# rhoby_motor_L6205.net
KiCad netlist of a schematic drawn in EAGLE
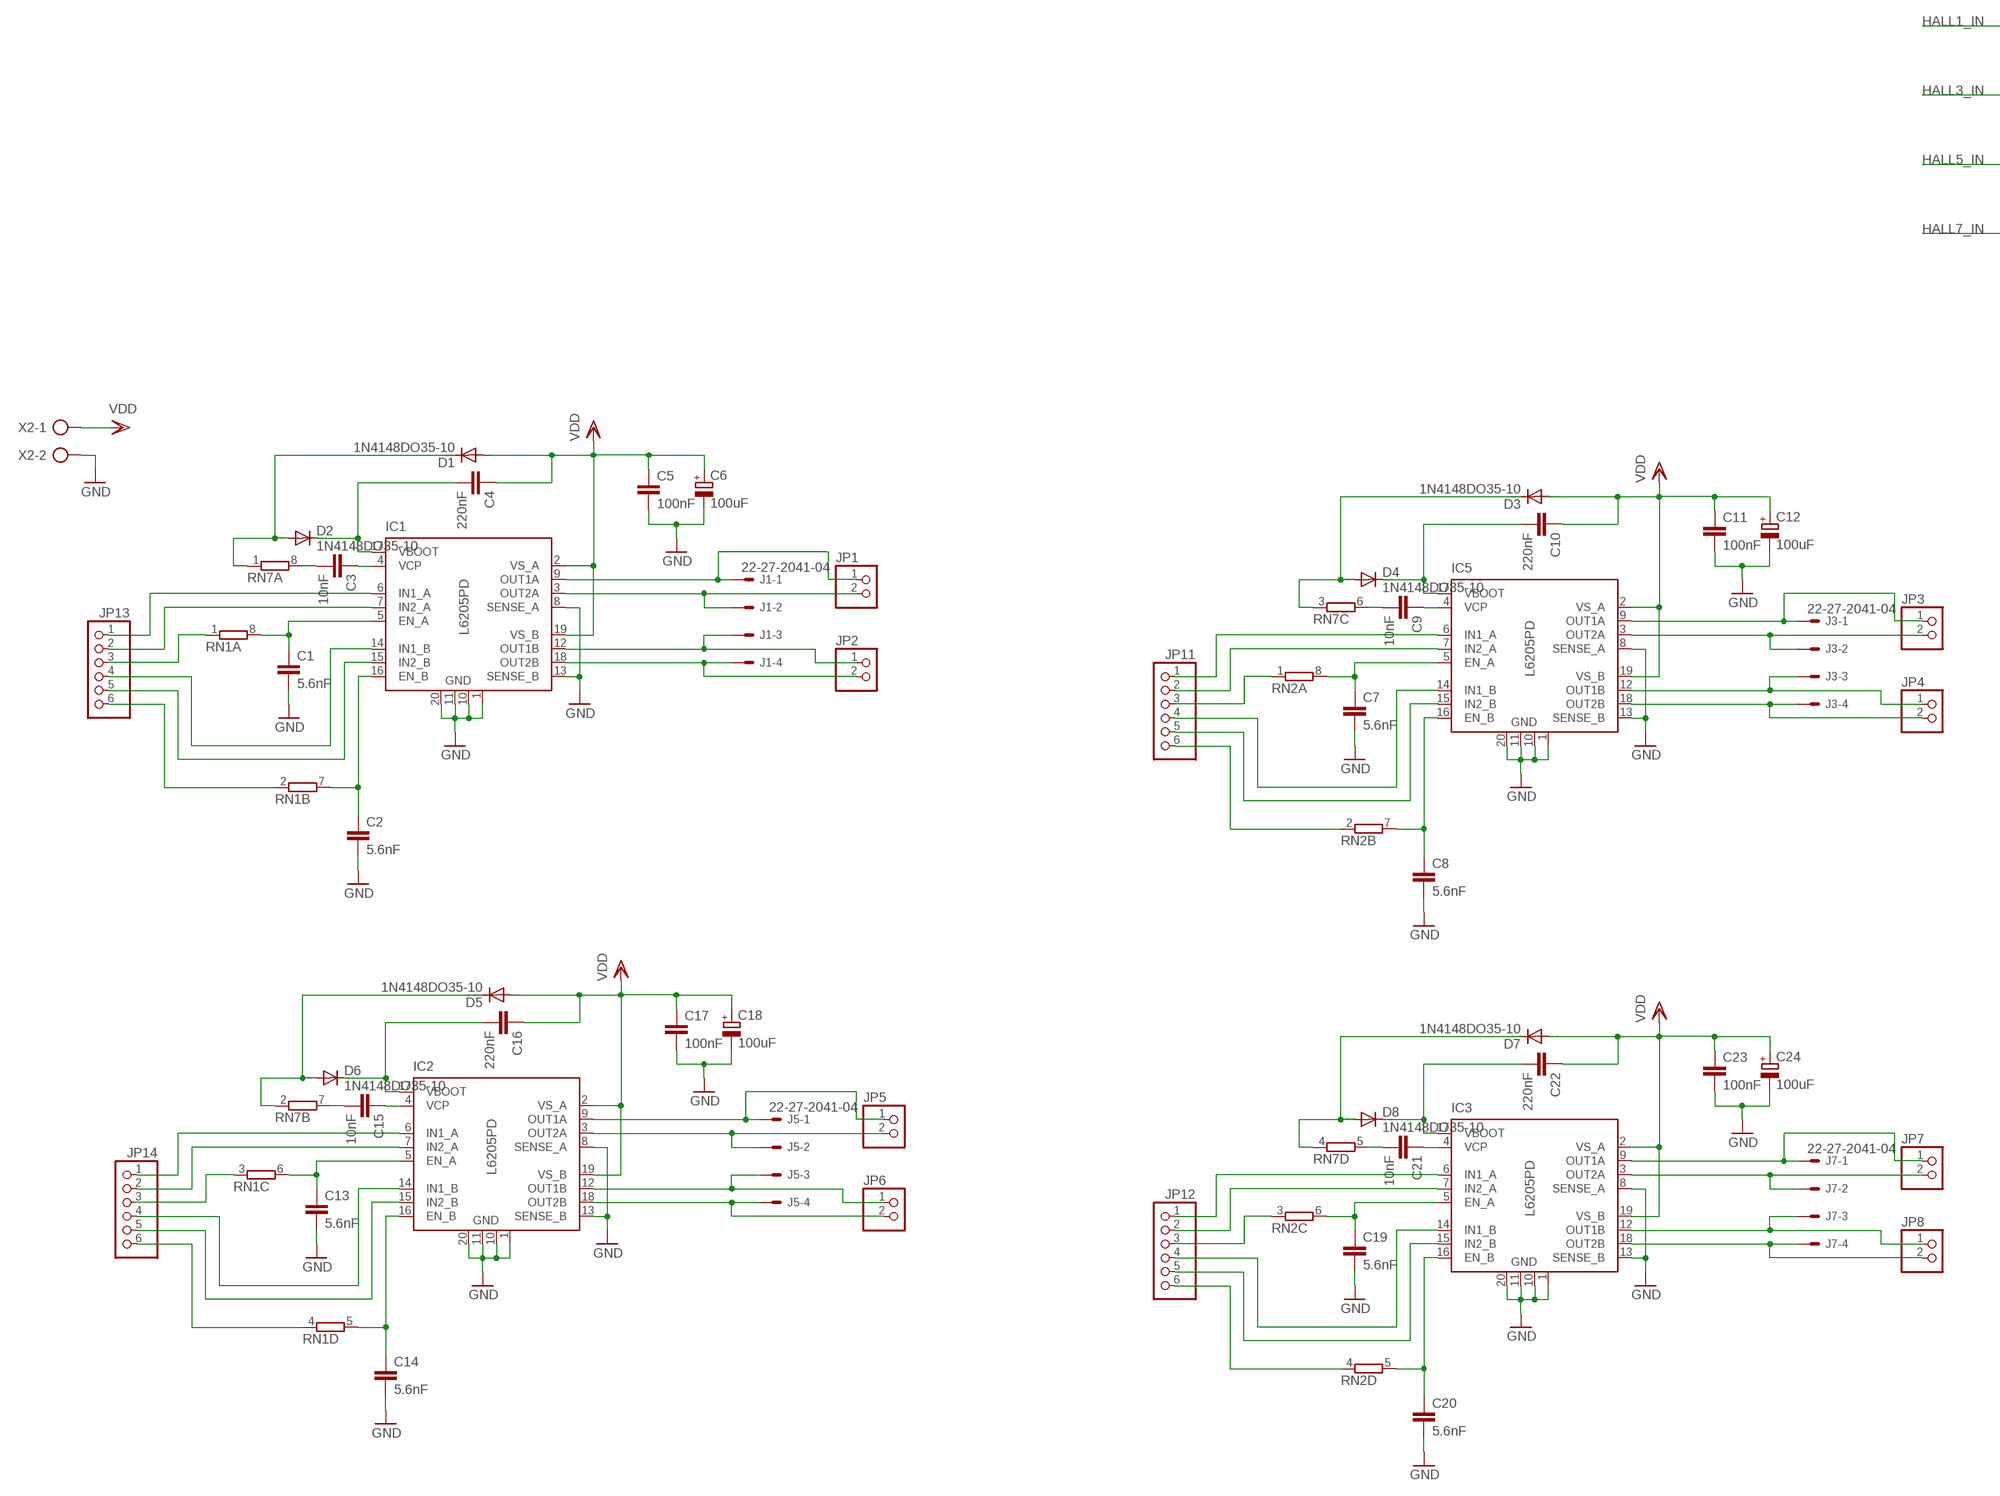
[diagram p0: schematic, sheet 1, part 1 of 2]
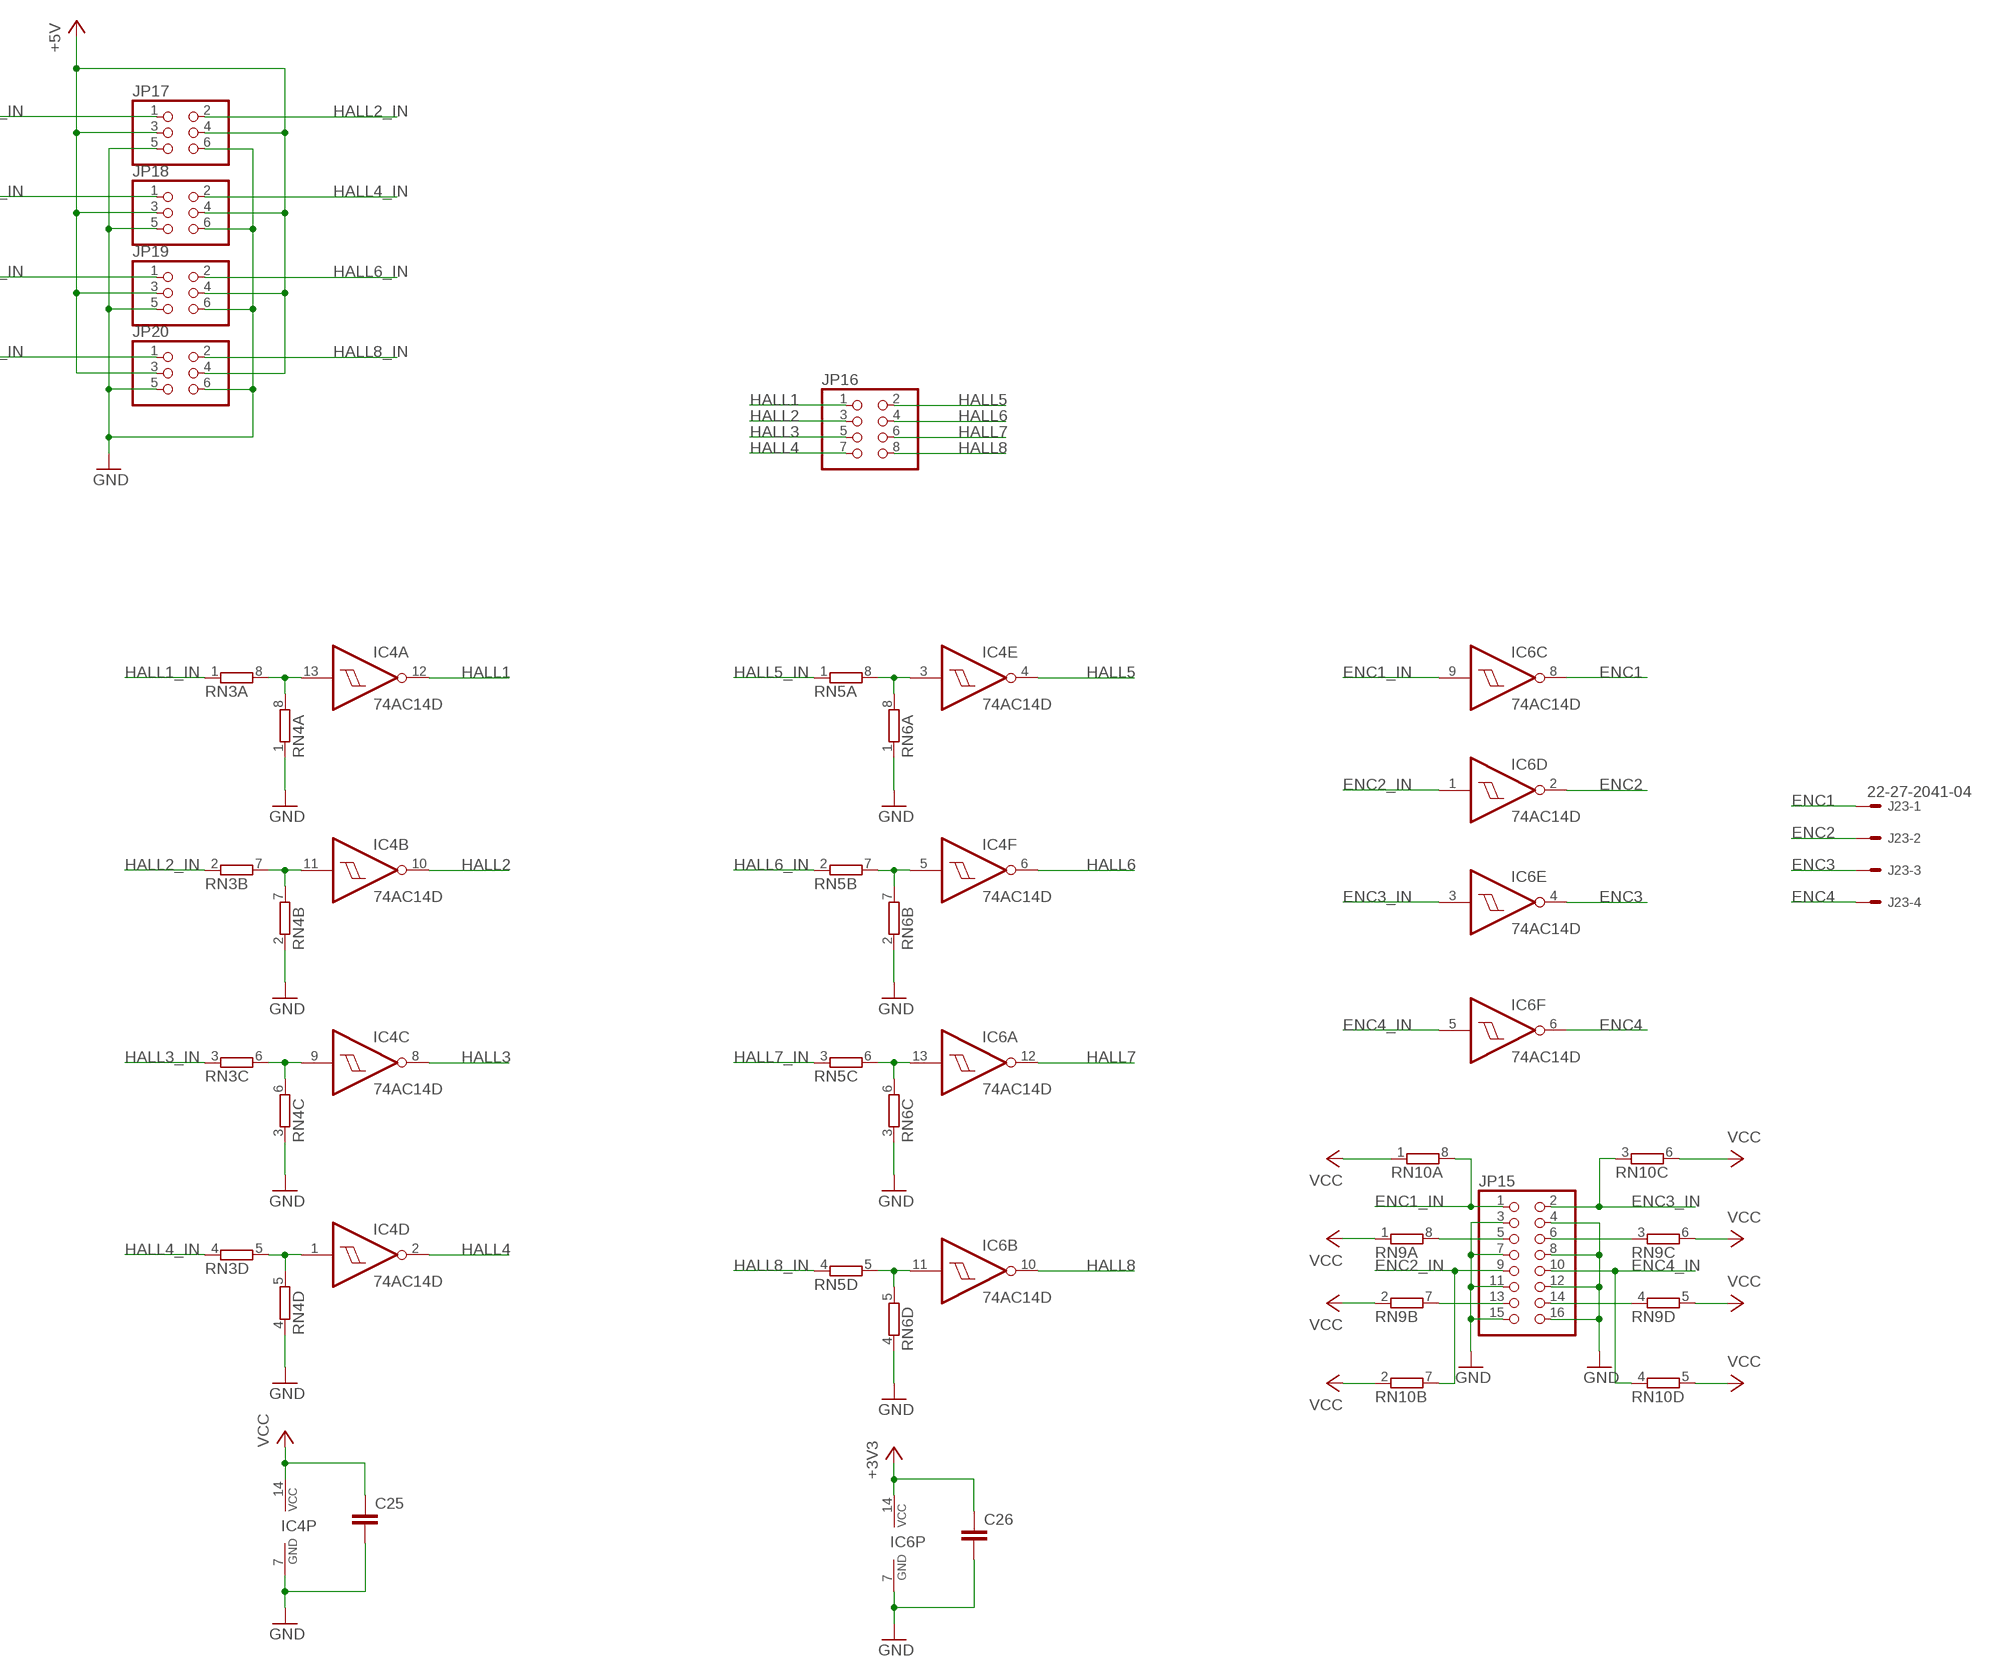
[diagram p1: schematic, sheet 1, part 2 of 2]

(export (version "E")
  (design (tool "Eeschema 10.0.6"))
  (components
    (comp (ref "C1")
      (value "5.6nF")
      (footprint "eagle-import:C0603K")
      (libsource (lib "eagle-import") (part "C-EUC0603K"))
    )
    (comp (ref "C2")
      (value "5.6nF")
      (footprint "eagle-import:C0603K")
      (libsource (lib "eagle-import") (part "C-EUC0603K"))
    )
    (comp (ref "C3")
      (value "10nF")
      (footprint "eagle-import:C0805K")
      (libsource (lib "eagle-import") (part "C-EUC0805K"))
    )
    (comp (ref "C4")
      (value "220nF")
      (footprint "eagle-import:C0805K")
      (libsource (lib "eagle-import") (part "C-EUC0805K"))
    )
    (comp (ref "C5")
      (value "100nF")
      (footprint "eagle-import:C2220K")
      (libsource (lib "eagle-import") (part "C-EUC2220K"))
    )
    (comp (ref "C6")
      (value "100uF")
      (footprint "eagle-import:SMC_D")
      (libsource (lib "eagle-import") (part "CPOL-EUSMCD"))
    )
    (comp (ref "C7")
      (value "5.6nF")
      (footprint "eagle-import:C0603K")
      (libsource (lib "eagle-import") (part "C-EUC0603K"))
    )
    (comp (ref "C8")
      (value "5.6nF")
      (footprint "eagle-import:C0603K")
      (libsource (lib "eagle-import") (part "C-EUC0603K"))
    )
    (comp (ref "C9")
      (value "10nF")
      (footprint "eagle-import:C0805K")
      (libsource (lib "eagle-import") (part "C-EUC0805K"))
    )
    (comp (ref "C10")
      (value "220nF")
      (footprint "eagle-import:C0805K")
      (libsource (lib "eagle-import") (part "C-EUC0805K"))
    )
    (comp (ref "C11")
      (value "100nF")
      (footprint "eagle-import:C2220K")
      (libsource (lib "eagle-import") (part "C-EUC2220K"))
    )
    (comp (ref "C12")
      (value "100uF")
      (footprint "eagle-import:SMC_D")
      (libsource (lib "eagle-import") (part "CPOL-EUSMCD"))
    )
    (comp (ref "C13")
      (value "5.6nF")
      (footprint "eagle-import:C0603K")
      (libsource (lib "eagle-import") (part "C-EUC0603K"))
    )
    (comp (ref "C14")
      (value "5.6nF")
      (footprint "eagle-import:C0603K")
      (libsource (lib "eagle-import") (part "C-EUC0603K"))
    )
    (comp (ref "C15")
      (value "10nF")
      (footprint "eagle-import:C0805K")
      (libsource (lib "eagle-import") (part "C-EUC0805K"))
    )
    (comp (ref "C16")
      (value "220nF")
      (footprint "eagle-import:C0805K")
      (libsource (lib "eagle-import") (part "C-EUC0805K"))
    )
    (comp (ref "C17")
      (value "100nF")
      (footprint "eagle-import:C2220K")
      (libsource (lib "eagle-import") (part "C-EUC2220K"))
    )
    (comp (ref "C18")
      (value "100uF")
      (footprint "eagle-import:SMC_D")
      (libsource (lib "eagle-import") (part "CPOL-EUSMCD"))
    )
    (comp (ref "C19")
      (value "5.6nF")
      (footprint "eagle-import:C0603K")
      (libsource (lib "eagle-import") (part "C-EUC0603K"))
    )
    (comp (ref "C20")
      (value "5.6nF")
      (footprint "eagle-import:C0603K")
      (libsource (lib "eagle-import") (part "C-EUC0603K"))
    )
    (comp (ref "C21")
      (value "10nF")
      (footprint "eagle-import:C0805K")
      (libsource (lib "eagle-import") (part "C-EUC0805K"))
    )
    (comp (ref "C22")
      (value "220nF")
      (footprint "eagle-import:C0805K")
      (libsource (lib "eagle-import") (part "C-EUC0805K"))
    )
    (comp (ref "C23")
      (value "100nF")
      (footprint "eagle-import:C2220K")
      (libsource (lib "eagle-import") (part "C-EUC2220K"))
    )
    (comp (ref "C24")
      (value "100uF")
      (footprint "eagle-import:SMC_D")
      (libsource (lib "eagle-import") (part "CPOL-EUSMCD"))
    )
    (comp (ref "C25")
      (value "C-EUC0603K")
      (footprint "eagle-import:C0603K")
      (libsource (lib "eagle-import") (part "C-EUC0603K"))
    )
    (comp (ref "C26")
      (value "C-EUC0603K")
      (footprint "eagle-import:C0603K")
      (libsource (lib "eagle-import") (part "C-EUC0603K"))
    )
    (comp (ref "D1")
      (value "1N4148DO35-10")
      (footprint "eagle-import:DO35-10")
      (libsource (lib "eagle-import") (part "1N4148DO35-10"))
    )
    (comp (ref "D2")
      (value "1N4148DO35-10")
      (footprint "eagle-import:DO35-10")
      (libsource (lib "eagle-import") (part "1N4148DO35-10"))
    )
    (comp (ref "D3")
      (value "1N4148DO35-10")
      (footprint "eagle-import:DO35-10")
      (libsource (lib "eagle-import") (part "1N4148DO35-10"))
    )
    (comp (ref "D4")
      (value "1N4148DO35-10")
      (footprint "eagle-import:DO35-10")
      (libsource (lib "eagle-import") (part "1N4148DO35-10"))
    )
    (comp (ref "D5")
      (value "1N4148DO35-10")
      (footprint "eagle-import:DO35-10")
      (libsource (lib "eagle-import") (part "1N4148DO35-10"))
    )
    (comp (ref "D6")
      (value "1N4148DO35-10")
      (footprint "eagle-import:DO35-10")
      (libsource (lib "eagle-import") (part "1N4148DO35-10"))
    )
    (comp (ref "D7")
      (value "1N4148DO35-10")
      (footprint "eagle-import:DO35-10")
      (libsource (lib "eagle-import") (part "1N4148DO35-10"))
    )
    (comp (ref "D8")
      (value "1N4148DO35-10")
      (footprint "eagle-import:DO35-10")
      (libsource (lib "eagle-import") (part "1N4148DO35-10"))
    )
    (comp (ref "IC1")
      (value "L6205PD")
      (footprint "eagle-import:POWERSO-20")
      (fields (field (name "MF") "Arrow Electronics"))
      (libsource (lib "eagle-import") (part "L6205PD"))
    )
    (comp (ref "IC2")
      (value "L6205PD")
      (footprint "eagle-import:POWERSO-20")
      (fields (field (name "MF") "Arrow Electronics"))
      (libsource (lib "eagle-import") (part "L6205PD"))
    )
    (comp (ref "IC3")
      (value "L6205PD")
      (footprint "eagle-import:POWERSO-20")
      (fields (field (name "MF") "Arrow Electronics"))
      (libsource (lib "eagle-import") (part "L6205PD"))
    )
    (comp (ref "IC4")
      (value "74AC14D")
      (footprint "eagle-import:SO14")
      (libsource (lib "eagle-import") (part "7414DAC"))
    )
    (comp (ref "IC5")
      (value "L6205PD")
      (footprint "eagle-import:POWERSO-20")
      (fields (field (name "MF") "Arrow Electronics"))
      (libsource (lib "eagle-import") (part "L6205PD"))
    )
    (comp (ref "IC6")
      (value "74AC14D")
      (footprint "eagle-import:SO14")
      (fields (field (name "SPICEPREFIX") "I"))
      (libsource (lib "eagle-import") (part "7414DAC"))
    )
    (comp (ref "J1")
      (value "22-27-2041-04")
      (footprint "eagle-import:6410-04")
      (fields (field (name "MF") "MOLEX"))
      (libsource (lib "eagle-import") (part "22-?-0427-2041"))
    )
    (comp (ref "J3")
      (value "22-27-2041-04")
      (footprint "eagle-import:6410-04")
      (fields (field (name "MF") "MOLEX"))
      (libsource (lib "eagle-import") (part "22-?-0427-2041"))
    )
    (comp (ref "J5")
      (value "22-27-2041-04")
      (footprint "eagle-import:6410-04")
      (fields (field (name "MF") "MOLEX"))
      (libsource (lib "eagle-import") (part "22-?-0427-2041"))
    )
    (comp (ref "J7")
      (value "22-27-2041-04")
      (footprint "eagle-import:6410-04")
      (fields (field (name "MF") "MOLEX"))
      (libsource (lib "eagle-import") (part "22-?-0427-2041"))
    )
    (comp (ref "J23")
      (value "22-27-2041-04")
      (footprint "eagle-import:6410-04")
      (fields (field (name "MF") "MOLEX"))
      (libsource (lib "eagle-import") (part "22-?-0427-2041"))
    )
    (comp (ref "JP1")
      (value "PINHD-1X2")
      (footprint "eagle-import:1X02")
      (libsource (lib "eagle-import") (part "PINHD-1X2"))
    )
    (comp (ref "JP2")
      (value "PINHD-1X2")
      (footprint "eagle-import:1X02")
      (libsource (lib "eagle-import") (part "PINHD-1X2"))
    )
    (comp (ref "JP3")
      (value "PINHD-1X2")
      (footprint "eagle-import:1X02")
      (libsource (lib "eagle-import") (part "PINHD-1X2"))
    )
    (comp (ref "JP4")
      (value "PINHD-1X2")
      (footprint "eagle-import:1X02")
      (libsource (lib "eagle-import") (part "PINHD-1X2"))
    )
    (comp (ref "JP5")
      (value "PINHD-1X2")
      (footprint "eagle-import:1X02")
      (libsource (lib "eagle-import") (part "PINHD-1X2"))
    )
    (comp (ref "JP6")
      (value "PINHD-1X2")
      (footprint "eagle-import:1X02")
      (libsource (lib "eagle-import") (part "PINHD-1X2"))
    )
    (comp (ref "JP7")
      (value "PINHD-1X2")
      (footprint "eagle-import:1X02")
      (libsource (lib "eagle-import") (part "PINHD-1X2"))
    )
    (comp (ref "JP8")
      (value "PINHD-1X2")
      (footprint "eagle-import:1X02")
      (libsource (lib "eagle-import") (part "PINHD-1X2"))
    )
    (comp (ref "JP11")
      (value "PINHD-1X6")
      (footprint "eagle-import:1X06")
      (libsource (lib "eagle-import") (part "PINHD-1X6"))
    )
    (comp (ref "JP12")
      (value "PINHD-1X6")
      (footprint "eagle-import:1X06")
      (libsource (lib "eagle-import") (part "PINHD-1X6"))
    )
    (comp (ref "JP13")
      (value "PINHD-1X6")
      (footprint "eagle-import:1X06")
      (libsource (lib "eagle-import") (part "PINHD-1X6"))
    )
    (comp (ref "JP14")
      (value "PINHD-1X6")
      (footprint "eagle-import:1X06")
      (libsource (lib "eagle-import") (part "PINHD-1X6"))
    )
    (comp (ref "JP15")
      (value "PINHD-2X8")
      (footprint "eagle-import:2X08")
      (libsource (lib "eagle-import") (part "PINHD-2X8"))
    )
    (comp (ref "JP16")
      (value "PINHD-2X4")
      (footprint "eagle-import:2X04")
      (libsource (lib "eagle-import") (part "PINHD-2X4"))
    )
    (comp (ref "JP17")
      (value "PINHD-2X3")
      (footprint "eagle-import:2X03")
      (libsource (lib "eagle-import") (part "PINHD-2X3"))
    )
    (comp (ref "JP18")
      (value "PINHD-2X3")
      (footprint "eagle-import:2X03")
      (libsource (lib "eagle-import") (part "PINHD-2X3"))
    )
    (comp (ref "JP19")
      (value "PINHD-2X3")
      (footprint "eagle-import:2X03")
      (libsource (lib "eagle-import") (part "PINHD-2X3"))
    )
    (comp (ref "JP20")
      (value "PINHD-2X3")
      (footprint "eagle-import:2X03")
      (libsource (lib "eagle-import") (part "PINHD-2X3"))
    )
    (comp (ref "RN1")
      (value "4R-NEXB38V")
      (footprint "eagle-import:EXB38V")
      (libsource (lib "eagle-import") (part "4R-NEXB38V"))
    )
    (comp (ref "RN2")
      (value "4R-NEXB38V")
      (footprint "eagle-import:EXB38V")
      (libsource (lib "eagle-import") (part "4R-NEXB38V"))
    )
    (comp (ref "RN3")
      (value "4R-NEXB38V")
      (footprint "eagle-import:EXB38V")
      (libsource (lib "eagle-import") (part "4R-NEXB38V"))
    )
    (comp (ref "RN4")
      (value "4R-NEXB38V")
      (footprint "eagle-import:EXB38V")
      (libsource (lib "eagle-import") (part "4R-NEXB38V"))
    )
    (comp (ref "RN5")
      (value "4R-NEXB38V")
      (footprint "eagle-import:EXB38V")
      (libsource (lib "eagle-import") (part "4R-NEXB38V"))
    )
    (comp (ref "RN6")
      (value "4R-NEXB38V")
      (footprint "eagle-import:EXB38V")
      (libsource (lib "eagle-import") (part "4R-NEXB38V"))
    )
    (comp (ref "RN7")
      (value "4R-NEXB38V")
      (footprint "eagle-import:EXB38V")
      (libsource (lib "eagle-import") (part "4R-NEXB38V"))
    )
    (comp (ref "RN9")
      (value "4R-NEXB38V")
      (footprint "eagle-import:EXB38V")
      (libsource (lib "eagle-import") (part "4R-NEXB38V"))
    )
    (comp (ref "RN10")
      (value "4R-NEXB38V")
      (footprint "eagle-import:EXB38V")
      (libsource (lib "eagle-import") (part "4R-NEXB38V"))
    )
    (comp (ref "X2")
      (value "AK500/2")
      (footprint "eagle-import:AK500_2")
      (libsource (lib "eagle-import") (part "AK500/2"))
    )
  )
  (nets
    (net (code "1") (name "+3V3") (class "Default")
      (node (ref "C26") (pin "1") (pinfunction "1_1") (pintype "passive"))
      (node (ref "IC6") (pin "14") (pinfunction "VCC_14") (pintype "power_in"))
    )
    (net (code "2") (name "+5V") (class "Default")
      (node (ref "JP17") (pin "3") (pinfunction "3_3") (pintype "passive"))
      (node (ref "JP17") (pin "4") (pinfunction "4_4") (pintype "passive"))
      (node (ref "JP18") (pin "3") (pinfunction "3_3") (pintype "passive"))
      (node (ref "JP18") (pin "4") (pinfunction "4_4") (pintype "passive"))
      (node (ref "JP19") (pin "3") (pinfunction "3_3") (pintype "passive"))
      (node (ref "JP19") (pin "4") (pinfunction "4_4") (pintype "passive"))
      (node (ref "JP20") (pin "3") (pinfunction "3_3") (pintype "passive"))
      (node (ref "JP20") (pin "4") (pinfunction "4_4") (pintype "passive"))
    )
    (net (code "3") (name "/ENC1") (class "Default")
      (node (ref "IC6") (pin "8") (pinfunction "O_8") (pintype "output"))
      (node (ref "J23") (pin "1") (pinfunction "S_1") (pintype "passive"))
    )
    (net (code "4") (name "/ENC1_IN") (class "Default")
      (node (ref "IC6") (pin "9") (pinfunction "I_9") (pintype "input"))
      (node (ref "JP15") (pin "1") (pinfunction "1_1") (pintype "passive"))
      (node (ref "RN10") (pin "8") (pinfunction "2_8") (pintype "passive"))
    )
    (net (code "5") (name "/ENC2") (class "Default")
      (node (ref "IC6") (pin "2") (pinfunction "O_2") (pintype "output"))
      (node (ref "J23") (pin "2") (pinfunction "S_2") (pintype "passive"))
    )
    (net (code "6") (name "/ENC2_IN") (class "Default")
      (node (ref "IC6") (pin "1") (pinfunction "I_1") (pintype "input"))
      (node (ref "JP15") (pin "9") (pinfunction "9_9") (pintype "passive"))
      (node (ref "RN10") (pin "7") (pinfunction "2_7") (pintype "passive"))
    )
    (net (code "7") (name "/ENC3") (class "Default")
      (node (ref "IC6") (pin "4") (pinfunction "O_4") (pintype "output"))
      (node (ref "J23") (pin "3") (pinfunction "S_3") (pintype "passive"))
    )
    (net (code "8") (name "/ENC3_IN") (class "Default")
      (node (ref "IC6") (pin "3") (pinfunction "I_3") (pintype "input"))
      (node (ref "JP15") (pin "2") (pinfunction "2_2") (pintype "passive"))
      (node (ref "RN10") (pin "3") (pinfunction "1_3") (pintype "passive"))
    )
    (net (code "9") (name "/ENC4") (class "Default")
      (node (ref "IC6") (pin "6") (pinfunction "O_6") (pintype "output"))
      (node (ref "J23") (pin "4") (pinfunction "S_4") (pintype "passive"))
    )
    (net (code "10") (name "/ENC4_IN") (class "Default")
      (node (ref "IC6") (pin "5") (pinfunction "I_5") (pintype "input"))
      (node (ref "JP15") (pin "10") (pinfunction "10_10") (pintype "passive"))
      (node (ref "RN10") (pin "4") (pinfunction "1_4") (pintype "passive"))
    )
    (net (code "11") (name "/HALL1") (class "Default")
      (node (ref "IC4") (pin "12") (pinfunction "O_12") (pintype "output"))
      (node (ref "JP16") (pin "1") (pinfunction "1_1") (pintype "passive"))
    )
    (net (code "12") (name "/HALL1_IN") (class "Default")
      (node (ref "JP17") (pin "1") (pinfunction "1_1") (pintype "passive"))
      (node (ref "RN3") (pin "1") (pinfunction "1_1") (pintype "passive"))
    )
    (net (code "13") (name "/HALL2") (class "Default")
      (node (ref "IC4") (pin "10") (pinfunction "O_10") (pintype "output"))
      (node (ref "JP16") (pin "3") (pinfunction "3_3") (pintype "passive"))
    )
    (net (code "14") (name "/HALL2_IN") (class "Default")
      (node (ref "JP17") (pin "2") (pinfunction "2_2") (pintype "passive"))
      (node (ref "RN3") (pin "2") (pinfunction "1_2") (pintype "passive"))
    )
    (net (code "15") (name "/HALL3") (class "Default")
      (node (ref "IC4") (pin "8") (pinfunction "O_8") (pintype "output"))
      (node (ref "JP16") (pin "5") (pinfunction "5_5") (pintype "passive"))
    )
    (net (code "16") (name "/HALL3_IN") (class "Default")
      (node (ref "JP18") (pin "1") (pinfunction "1_1") (pintype "passive"))
      (node (ref "RN3") (pin "3") (pinfunction "1_3") (pintype "passive"))
    )
    (net (code "17") (name "/HALL4") (class "Default")
      (node (ref "IC4") (pin "2") (pinfunction "O_2") (pintype "output"))
      (node (ref "JP16") (pin "7") (pinfunction "7_7") (pintype "passive"))
    )
    (net (code "18") (name "/HALL4_IN") (class "Default")
      (node (ref "JP18") (pin "2") (pinfunction "2_2") (pintype "passive"))
      (node (ref "RN3") (pin "4") (pinfunction "1_4") (pintype "passive"))
    )
    (net (code "19") (name "/HALL5") (class "Default")
      (node (ref "IC4") (pin "4") (pinfunction "O_4") (pintype "output"))
      (node (ref "JP16") (pin "2") (pinfunction "2_2") (pintype "passive"))
    )
    (net (code "20") (name "/HALL5_IN") (class "Default")
      (node (ref "JP19") (pin "1") (pinfunction "1_1") (pintype "passive"))
      (node (ref "RN5") (pin "1") (pinfunction "1_1") (pintype "passive"))
    )
    (net (code "21") (name "/HALL6") (class "Default")
      (node (ref "IC4") (pin "6") (pinfunction "O_6") (pintype "output"))
      (node (ref "JP16") (pin "4") (pinfunction "4_4") (pintype "passive"))
    )
    (net (code "22") (name "/HALL6_IN") (class "Default")
      (node (ref "JP19") (pin "2") (pinfunction "2_2") (pintype "passive"))
      (node (ref "RN5") (pin "2") (pinfunction "1_2") (pintype "passive"))
    )
    (net (code "23") (name "/HALL7") (class "Default")
      (node (ref "IC6") (pin "12") (pinfunction "O_12") (pintype "output"))
      (node (ref "JP16") (pin "6") (pinfunction "6_6") (pintype "passive"))
    )
    (net (code "24") (name "/HALL7_IN") (class "Default")
      (node (ref "JP20") (pin "1") (pinfunction "1_1") (pintype "passive"))
      (node (ref "RN5") (pin "3") (pinfunction "1_3") (pintype "passive"))
    )
    (net (code "25") (name "/HALL8") (class "Default")
      (node (ref "IC6") (pin "10") (pinfunction "O_10") (pintype "output"))
      (node (ref "JP16") (pin "8") (pinfunction "8_8") (pintype "passive"))
    )
    (net (code "26") (name "/HALL8_IN") (class "Default")
      (node (ref "JP20") (pin "2") (pinfunction "2_2") (pintype "passive"))
      (node (ref "RN5") (pin "4") (pinfunction "1_4") (pintype "passive"))
    )
    (net (code "27") (name "GND") (class "Default")
      (node (ref "C1") (pin "2") (pinfunction "2_2") (pintype "passive"))
      (node (ref "C11") (pin "2") (pinfunction "2_2") (pintype "passive"))
      (node (ref "C12") (pin "-") (pinfunction "-_-") (pintype "passive"))
      (node (ref "C13") (pin "2") (pinfunction "2_2") (pintype "passive"))
      (node (ref "C14") (pin "2") (pinfunction "2_2") (pintype "passive"))
      (node (ref "C17") (pin "2") (pinfunction "2_2") (pintype "passive"))
      (node (ref "C18") (pin "-") (pinfunction "-_-") (pintype "passive"))
      (node (ref "C19") (pin "2") (pinfunction "2_2") (pintype "passive"))
      (node (ref "C2") (pin "2") (pinfunction "2_2") (pintype "passive"))
      (node (ref "C20") (pin "2") (pinfunction "2_2") (pintype "passive"))
      (node (ref "C23") (pin "2") (pinfunction "2_2") (pintype "passive"))
      (node (ref "C24") (pin "-") (pinfunction "-_-") (pintype "passive"))
      (node (ref "C25") (pin "2") (pinfunction "2_2") (pintype "passive"))
      (node (ref "C26") (pin "2") (pinfunction "2_2") (pintype "passive"))
      (node (ref "C5") (pin "2") (pinfunction "2_2") (pintype "passive"))
      (node (ref "C6") (pin "-") (pinfunction "-_-") (pintype "passive"))
      (node (ref "C7") (pin "2") (pinfunction "2_2") (pintype "passive"))
      (node (ref "C8") (pin "2") (pinfunction "2_2") (pintype "passive"))
      (node (ref "IC1") (pin "1") (pinfunction "GND_1") (pintype "power_in"))
      (node (ref "IC1") (pin "10") (pinfunction "GND_10") (pintype "power_in"))
      (node (ref "IC1") (pin "11") (pinfunction "GND_11") (pintype "power_in"))
      (node (ref "IC1") (pin "13") (pinfunction "SENSE_B_13") (pintype "input"))
      (node (ref "IC1") (pin "20") (pinfunction "GND_20") (pintype "power_in"))
      (node (ref "IC1") (pin "8") (pinfunction "SENSE_A_8") (pintype "input"))
      (node (ref "IC2") (pin "1") (pinfunction "GND_1") (pintype "power_in"))
      (node (ref "IC2") (pin "10") (pinfunction "GND_10") (pintype "power_in"))
      (node (ref "IC2") (pin "11") (pinfunction "GND_11") (pintype "power_in"))
      (node (ref "IC2") (pin "13") (pinfunction "SENSE_B_13") (pintype "input"))
      (node (ref "IC2") (pin "20") (pinfunction "GND_20") (pintype "power_in"))
      (node (ref "IC2") (pin "8") (pinfunction "SENSE_A_8") (pintype "input"))
      (node (ref "IC3") (pin "1") (pinfunction "GND_1") (pintype "power_in"))
      (node (ref "IC3") (pin "10") (pinfunction "GND_10") (pintype "power_in"))
      (node (ref "IC3") (pin "11") (pinfunction "GND_11") (pintype "power_in"))
      (node (ref "IC3") (pin "13") (pinfunction "SENSE_B_13") (pintype "input"))
      (node (ref "IC3") (pin "20") (pinfunction "GND_20") (pintype "power_in"))
      (node (ref "IC3") (pin "8") (pinfunction "SENSE_A_8") (pintype "input"))
      (node (ref "IC4") (pin "7") (pinfunction "GND_7") (pintype "power_in"))
      (node (ref "IC5") (pin "1") (pinfunction "GND_1") (pintype "power_in"))
      (node (ref "IC5") (pin "10") (pinfunction "GND_10") (pintype "power_in"))
      (node (ref "IC5") (pin "11") (pinfunction "GND_11") (pintype "power_in"))
      (node (ref "IC5") (pin "13") (pinfunction "SENSE_B_13") (pintype "input"))
      (node (ref "IC5") (pin "20") (pinfunction "GND_20") (pintype "power_in"))
      (node (ref "IC5") (pin "8") (pinfunction "SENSE_A_8") (pintype "input"))
      (node (ref "IC6") (pin "7") (pinfunction "GND_7") (pintype "power_in"))
      (node (ref "JP15") (pin "11") (pinfunction "11_11") (pintype "passive"))
      (node (ref "JP15") (pin "12") (pinfunction "12_12") (pintype "passive"))
      (node (ref "JP15") (pin "15") (pinfunction "15_15") (pintype "passive"))
      (node (ref "JP15") (pin "16") (pinfunction "16_16") (pintype "passive"))
      (node (ref "JP15") (pin "3") (pinfunction "3_3") (pintype "passive"))
      (node (ref "JP15") (pin "4") (pinfunction "4_4") (pintype "passive"))
      (node (ref "JP15") (pin "7") (pinfunction "7_7") (pintype "passive"))
      (node (ref "JP15") (pin "8") (pinfunction "8_8") (pintype "passive"))
      (node (ref "JP17") (pin "5") (pinfunction "5_5") (pintype "passive"))
      (node (ref "JP17") (pin "6") (pinfunction "6_6") (pintype "passive"))
      (node (ref "JP18") (pin "5") (pinfunction "5_5") (pintype "passive"))
      (node (ref "JP18") (pin "6") (pinfunction "6_6") (pintype "passive"))
      (node (ref "JP19") (pin "5") (pinfunction "5_5") (pintype "passive"))
      (node (ref "JP19") (pin "6") (pinfunction "6_6") (pintype "passive"))
      (node (ref "JP20") (pin "5") (pinfunction "5_5") (pintype "passive"))
      (node (ref "JP20") (pin "6") (pinfunction "6_6") (pintype "passive"))
      (node (ref "RN4") (pin "1") (pinfunction "1_1") (pintype "passive"))
      (node (ref "RN4") (pin "2") (pinfunction "1_2") (pintype "passive"))
      (node (ref "RN4") (pin "3") (pinfunction "1_3") (pintype "passive"))
      (node (ref "RN4") (pin "4") (pinfunction "1_4") (pintype "passive"))
      (node (ref "RN6") (pin "1") (pinfunction "1_1") (pintype "passive"))
      (node (ref "RN6") (pin "2") (pinfunction "1_2") (pintype "passive"))
      (node (ref "RN6") (pin "3") (pinfunction "1_3") (pintype "passive"))
      (node (ref "RN6") (pin "4") (pinfunction "1_4") (pintype "passive"))
      (node (ref "X2") (pin "2") (pinfunction "KL_2") (pintype "passive"))
    )
    (net (code "28") (name "Net-(D1-PadC)") (class "Default")
      (node (ref "D1") (pin "C") (pinfunction "C_C") (pintype "passive"))
      (node (ref "D2") (pin "A") (pinfunction "A_A") (pintype "passive"))
      (node (ref "RN7") (pin "1") (pinfunction "1_1") (pintype "passive"))
    )
    (net (code "29") (name "Net-(IC1-EN_A)") (class "Default")
      (node (ref "C1") (pin "1") (pinfunction "1_1") (pintype "passive"))
      (node (ref "IC1") (pin "5") (pinfunction "EN_A_5") (pintype "input"))
      (node (ref "RN1") (pin "8") (pinfunction "2_8") (pintype "passive"))
    )
    (net (code "30") (name "Net-(IC1-EN_B)") (class "Default")
      (node (ref "C2") (pin "1") (pinfunction "1_1") (pintype "passive"))
      (node (ref "IC1") (pin "16") (pinfunction "EN_B_16") (pintype "input"))
      (node (ref "RN1") (pin "7") (pinfunction "2_7") (pintype "passive"))
    )
    (net (code "31") (name "Net-(IC1-IN1_A)") (class "Default")
      (node (ref "IC1") (pin "6") (pinfunction "IN1_A_6") (pintype "input"))
      (node (ref "JP13") (pin "1") (pinfunction "1_1") (pintype "passive"))
    )
    (net (code "32") (name "Net-(IC1-IN1_B)") (class "Default")
      (node (ref "IC1") (pin "14") (pinfunction "IN1_B_14") (pintype "input"))
      (node (ref "JP13") (pin "4") (pinfunction "4_4") (pintype "passive"))
    )
    (net (code "33") (name "Net-(IC1-IN2_A)") (class "Default")
      (node (ref "IC1") (pin "7") (pinfunction "IN2_A_7") (pintype "input"))
      (node (ref "JP13") (pin "2") (pinfunction "2_2") (pintype "passive"))
    )
    (net (code "34") (name "Net-(IC1-IN2_B)") (class "Default")
      (node (ref "IC1") (pin "15") (pinfunction "IN2_B_15") (pintype "input"))
      (node (ref "JP13") (pin "5") (pinfunction "5_5") (pintype "passive"))
    )
    (net (code "35") (name "Net-(IC1-OUT1A)") (class "Default")
      (node (ref "IC1") (pin "9") (pinfunction "OUT1A_9") (pintype "output"))
      (node (ref "J1") (pin "1") (pinfunction "S_1") (pintype "passive"))
      (node (ref "JP1") (pin "1") (pinfunction "1_1") (pintype "passive"))
    )
    (net (code "36") (name "Net-(IC1-OUT1B)") (class "Default")
      (node (ref "IC1") (pin "12") (pinfunction "OUT1B_12") (pintype "output"))
      (node (ref "J1") (pin "3") (pinfunction "S_3") (pintype "passive"))
      (node (ref "JP2") (pin "1") (pinfunction "1_1") (pintype "passive"))
    )
    (net (code "37") (name "Net-(IC1-OUT2A)") (class "Default")
      (node (ref "IC1") (pin "3") (pinfunction "OUT2A_3") (pintype "output"))
      (node (ref "J1") (pin "2") (pinfunction "S_2") (pintype "passive"))
      (node (ref "JP1") (pin "2") (pinfunction "2_2") (pintype "passive"))
    )
    (net (code "38") (name "Net-(IC1-OUT2B)") (class "Default")
      (node (ref "IC1") (pin "18") (pinfunction "OUT2B_18") (pintype "output"))
      (node (ref "J1") (pin "4") (pinfunction "S_4") (pintype "passive"))
      (node (ref "JP2") (pin "2") (pinfunction "2_2") (pintype "passive"))
    )
    (net (code "39") (name "Net-(IC1-VBOOT)") (class "Default")
      (node (ref "C4") (pin "2") (pinfunction "2_2") (pintype "passive"))
      (node (ref "D2") (pin "C") (pinfunction "C_C") (pintype "passive"))
      (node (ref "IC1") (pin "17") (pinfunction "VBOOT_17") (pintype "power_in"))
    )
    (net (code "40") (name "Net-(IC1-VCP)") (class "Default")
      (node (ref "C3") (pin "1") (pinfunction "1_1") (pintype "passive"))
      (node (ref "IC1") (pin "4") (pinfunction "VCP_4") (pintype "power_in"))
    )
    (net (code "41") (name "Net-(IC2-EN_A)") (class "Default")
      (node (ref "C13") (pin "1") (pinfunction "1_1") (pintype "passive"))
      (node (ref "IC2") (pin "5") (pinfunction "EN_A_5") (pintype "input"))
      (node (ref "RN1") (pin "6") (pinfunction "2_6") (pintype "passive"))
    )
    (net (code "42") (name "Net-(IC2-EN_B)") (class "Default")
      (node (ref "C14") (pin "1") (pinfunction "1_1") (pintype "passive"))
      (node (ref "IC2") (pin "16") (pinfunction "EN_B_16") (pintype "input"))
      (node (ref "RN1") (pin "5") (pinfunction "2_5") (pintype "passive"))
    )
    (net (code "43") (name "Net-(IC2-IN1_A)") (class "Default")
      (node (ref "IC2") (pin "6") (pinfunction "IN1_A_6") (pintype "input"))
      (node (ref "JP14") (pin "1") (pinfunction "1_1") (pintype "passive"))
    )
    (net (code "44") (name "Net-(IC2-IN1_B)") (class "Default")
      (node (ref "IC2") (pin "14") (pinfunction "IN1_B_14") (pintype "input"))
      (node (ref "JP14") (pin "4") (pinfunction "4_4") (pintype "passive"))
    )
    (net (code "45") (name "Net-(IC2-IN2_A)") (class "Default")
      (node (ref "IC2") (pin "7") (pinfunction "IN2_A_7") (pintype "input"))
      (node (ref "JP14") (pin "2") (pinfunction "2_2") (pintype "passive"))
    )
    (net (code "46") (name "Net-(IC2-IN2_B)") (class "Default")
      (node (ref "IC2") (pin "15") (pinfunction "IN2_B_15") (pintype "input"))
      (node (ref "JP14") (pin "5") (pinfunction "5_5") (pintype "passive"))
    )
    (net (code "47") (name "Net-(IC2-OUT1A)") (class "Default")
      (node (ref "IC2") (pin "9") (pinfunction "OUT1A_9") (pintype "output"))
      (node (ref "J5") (pin "1") (pinfunction "S_1") (pintype "passive"))
      (node (ref "JP5") (pin "1") (pinfunction "1_1") (pintype "passive"))
    )
    (net (code "48") (name "Net-(IC2-OUT1B)") (class "Default")
      (node (ref "IC2") (pin "12") (pinfunction "OUT1B_12") (pintype "output"))
      (node (ref "J5") (pin "3") (pinfunction "S_3") (pintype "passive"))
      (node (ref "JP6") (pin "1") (pinfunction "1_1") (pintype "passive"))
    )
    (net (code "49") (name "Net-(IC2-OUT2A)") (class "Default")
      (node (ref "IC2") (pin "3") (pinfunction "OUT2A_3") (pintype "output"))
      (node (ref "J5") (pin "2") (pinfunction "S_2") (pintype "passive"))
      (node (ref "JP5") (pin "2") (pinfunction "2_2") (pintype "passive"))
    )
    (net (code "50") (name "Net-(IC2-OUT2B)") (class "Default")
      (node (ref "IC2") (pin "18") (pinfunction "OUT2B_18") (pintype "output"))
      (node (ref "J5") (pin "4") (pinfunction "S_4") (pintype "passive"))
      (node (ref "JP6") (pin "2") (pinfunction "2_2") (pintype "passive"))
    )
    (net (code "51") (name "Net-(IC2-VBOOT)") (class "Default")
      (node (ref "C16") (pin "2") (pinfunction "2_2") (pintype "passive"))
      (node (ref "D6") (pin "C") (pinfunction "C_C") (pintype "passive"))
      (node (ref "IC2") (pin "17") (pinfunction "VBOOT_17") (pintype "power_in"))
    )
    (net (code "52") (name "Net-(IC2-VCP)") (class "Default")
      (node (ref "C15") (pin "1") (pinfunction "1_1") (pintype "passive"))
      (node (ref "IC2") (pin "4") (pinfunction "VCP_4") (pintype "power_in"))
    )
    (net (code "53") (name "Net-(IC3-EN_A)") (class "Default")
      (node (ref "C19") (pin "1") (pinfunction "1_1") (pintype "passive"))
      (node (ref "IC3") (pin "5") (pinfunction "EN_A_5") (pintype "input"))
      (node (ref "RN2") (pin "6") (pinfunction "2_6") (pintype "passive"))
    )
    (net (code "54") (name "Net-(IC3-EN_B)") (class "Default")
      (node (ref "C20") (pin "1") (pinfunction "1_1") (pintype "passive"))
      (node (ref "IC3") (pin "16") (pinfunction "EN_B_16") (pintype "input"))
      (node (ref "RN2") (pin "5") (pinfunction "2_5") (pintype "passive"))
    )
    (net (code "55") (name "Net-(IC3-IN1_A)") (class "Default")
      (node (ref "IC3") (pin "6") (pinfunction "IN1_A_6") (pintype "input"))
      (node (ref "JP12") (pin "1") (pinfunction "1_1") (pintype "passive"))
    )
    (net (code "56") (name "Net-(IC3-IN1_B)") (class "Default")
      (node (ref "IC3") (pin "14") (pinfunction "IN1_B_14") (pintype "input"))
      (node (ref "JP12") (pin "4") (pinfunction "4_4") (pintype "passive"))
    )
    (net (code "57") (name "Net-(IC3-IN2_A)") (class "Default")
      (node (ref "IC3") (pin "7") (pinfunction "IN2_A_7") (pintype "input"))
      (node (ref "JP12") (pin "2") (pinfunction "2_2") (pintype "passive"))
    )
    (net (code "58") (name "Net-(IC3-IN2_B)") (class "Default")
      (node (ref "IC3") (pin "15") (pinfunction "IN2_B_15") (pintype "input"))
      (node (ref "JP12") (pin "5") (pinfunction "5_5") (pintype "passive"))
    )
    (net (code "59") (name "Net-(IC3-OUT1A)") (class "Default")
      (node (ref "IC3") (pin "9") (pinfunction "OUT1A_9") (pintype "output"))
      (node (ref "J7") (pin "1") (pinfunction "S_1") (pintype "passive"))
      (node (ref "JP7") (pin "1") (pinfunction "1_1") (pintype "passive"))
    )
    (net (code "60") (name "Net-(IC3-OUT1B)") (class "Default")
      (node (ref "IC3") (pin "12") (pinfunction "OUT1B_12") (pintype "output"))
      (node (ref "J7") (pin "3") (pinfunction "S_3") (pintype "passive"))
      (node (ref "JP8") (pin "1") (pinfunction "1_1") (pintype "passive"))
    )
    (net (code "61") (name "Net-(IC3-OUT2A)") (class "Default")
      (node (ref "IC3") (pin "3") (pinfunction "OUT2A_3") (pintype "output"))
      (node (ref "J7") (pin "2") (pinfunction "S_2") (pintype "passive"))
      (node (ref "JP7") (pin "2") (pinfunction "2_2") (pintype "passive"))
    )
    (net (code "62") (name "Net-(IC3-OUT2B)") (class "Default")
      (node (ref "IC3") (pin "18") (pinfunction "OUT2B_18") (pintype "output"))
      (node (ref "J7") (pin "4") (pinfunction "S_4") (pintype "passive"))
      (node (ref "JP8") (pin "2") (pinfunction "2_2") (pintype "passive"))
    )
    (net (code "63") (name "Net-(IC3-VBOOT)") (class "Default")
      (node (ref "C22") (pin "2") (pinfunction "2_2") (pintype "passive"))
      (node (ref "D8") (pin "C") (pinfunction "C_C") (pintype "passive"))
      (node (ref "IC3") (pin "17") (pinfunction "VBOOT_17") (pintype "power_in"))
    )
    (net (code "64") (name "Net-(IC3-VCP)") (class "Default")
      (node (ref "C21") (pin "1") (pinfunction "1_1") (pintype "passive"))
      (node (ref "IC3") (pin "4") (pinfunction "VCP_4") (pintype "power_in"))
    )
    (net (code "65") (name "Net-(IC4A-I)") (class "Default")
      (node (ref "IC4") (pin "13") (pinfunction "I_13") (pintype "input"))
      (node (ref "RN3") (pin "8") (pinfunction "2_8") (pintype "passive"))
      (node (ref "RN4") (pin "8") (pinfunction "2_8") (pintype "passive"))
    )
    (net (code "66") (name "Net-(IC4B-I)") (class "Default")
      (node (ref "IC4") (pin "11") (pinfunction "I_11") (pintype "input"))
      (node (ref "RN3") (pin "7") (pinfunction "2_7") (pintype "passive"))
      (node (ref "RN4") (pin "7") (pinfunction "2_7") (pintype "passive"))
    )
    (net (code "67") (name "Net-(IC4C-I)") (class "Default")
      (node (ref "IC4") (pin "9") (pinfunction "I_9") (pintype "input"))
      (node (ref "RN3") (pin "6") (pinfunction "2_6") (pintype "passive"))
      (node (ref "RN4") (pin "6") (pinfunction "2_6") (pintype "passive"))
    )
    (net (code "68") (name "Net-(IC4D-I)") (class "Default")
      (node (ref "IC4") (pin "1") (pinfunction "I_1") (pintype "input"))
      (node (ref "RN3") (pin "5") (pinfunction "2_5") (pintype "passive"))
      (node (ref "RN4") (pin "5") (pinfunction "2_5") (pintype "passive"))
    )
    (net (code "69") (name "Net-(IC4E-I)") (class "Default")
      (node (ref "IC4") (pin "3") (pinfunction "I_3") (pintype "input"))
      (node (ref "RN5") (pin "8") (pinfunction "2_8") (pintype "passive"))
      (node (ref "RN6") (pin "8") (pinfunction "2_8") (pintype "passive"))
    )
    (net (code "70") (name "Net-(IC4F-I)") (class "Default")
      (node (ref "IC4") (pin "5") (pinfunction "I_5") (pintype "input"))
      (node (ref "RN5") (pin "7") (pinfunction "2_7") (pintype "passive"))
      (node (ref "RN6") (pin "7") (pinfunction "2_7") (pintype "passive"))
    )
    (net (code "71") (name "Net-(IC5-EN_A)") (class "Default")
      (node (ref "C7") (pin "1") (pinfunction "1_1") (pintype "passive"))
      (node (ref "IC5") (pin "5") (pinfunction "EN_A_5") (pintype "input"))
      (node (ref "RN2") (pin "8") (pinfunction "2_8") (pintype "passive"))
    )
    (net (code "72") (name "Net-(IC5-EN_B)") (class "Default")
      (node (ref "C8") (pin "1") (pinfunction "1_1") (pintype "passive"))
      (node (ref "IC5") (pin "16") (pinfunction "EN_B_16") (pintype "input"))
      (node (ref "RN2") (pin "7") (pinfunction "2_7") (pintype "passive"))
    )
    (net (code "73") (name "Net-(IC5-IN1_A)") (class "Default")
      (node (ref "IC5") (pin "6") (pinfunction "IN1_A_6") (pintype "input"))
      (node (ref "JP11") (pin "1") (pinfunction "1_1") (pintype "passive"))
    )
    (net (code "74") (name "Net-(IC5-IN1_B)") (class "Default")
      (node (ref "IC5") (pin "14") (pinfunction "IN1_B_14") (pintype "input"))
      (node (ref "JP11") (pin "4") (pinfunction "4_4") (pintype "passive"))
    )
    (net (code "75") (name "Net-(IC5-IN2_A)") (class "Default")
      (node (ref "IC5") (pin "7") (pinfunction "IN2_A_7") (pintype "input"))
      (node (ref "JP11") (pin "2") (pinfunction "2_2") (pintype "passive"))
    )
    (net (code "76") (name "Net-(IC5-IN2_B)") (class "Default")
      (node (ref "IC5") (pin "15") (pinfunction "IN2_B_15") (pintype "input"))
      (node (ref "JP11") (pin "5") (pinfunction "5_5") (pintype "passive"))
    )
    (net (code "77") (name "Net-(IC5-OUT1A)") (class "Default")
      (node (ref "IC5") (pin "9") (pinfunction "OUT1A_9") (pintype "output"))
      (node (ref "J3") (pin "1") (pinfunction "S_1") (pintype "passive"))
      (node (ref "JP3") (pin "1") (pinfunction "1_1") (pintype "passive"))
    )
    (net (code "78") (name "Net-(IC5-OUT1B)") (class "Default")
      (node (ref "IC5") (pin "12") (pinfunction "OUT1B_12") (pintype "output"))
      (node (ref "J3") (pin "3") (pinfunction "S_3") (pintype "passive"))
      (node (ref "JP4") (pin "1") (pinfunction "1_1") (pintype "passive"))
    )
    (net (code "79") (name "Net-(IC5-OUT2A)") (class "Default")
      (node (ref "IC5") (pin "3") (pinfunction "OUT2A_3") (pintype "output"))
      (node (ref "J3") (pin "2") (pinfunction "S_2") (pintype "passive"))
      (node (ref "JP3") (pin "2") (pinfunction "2_2") (pintype "passive"))
    )
    (net (code "80") (name "Net-(IC5-OUT2B)") (class "Default")
      (node (ref "IC5") (pin "18") (pinfunction "OUT2B_18") (pintype "output"))
      (node (ref "J3") (pin "4") (pinfunction "S_4") (pintype "passive"))
      (node (ref "JP4") (pin "2") (pinfunction "2_2") (pintype "passive"))
    )
    (net (code "81") (name "Net-(IC5-VBOOT)") (class "Default")
      (node (ref "C10") (pin "2") (pinfunction "2_2") (pintype "passive"))
      (node (ref "D4") (pin "C") (pinfunction "C_C") (pintype "passive"))
      (node (ref "IC5") (pin "17") (pinfunction "VBOOT_17") (pintype "power_in"))
    )
    (net (code "82") (name "Net-(IC5-VCP)") (class "Default")
      (node (ref "C9") (pin "1") (pinfunction "1_1") (pintype "passive"))
      (node (ref "IC5") (pin "4") (pinfunction "VCP_4") (pintype "power_in"))
    )
    (net (code "83") (name "Net-(IC6A-I)") (class "Default")
      (node (ref "IC6") (pin "13") (pinfunction "I_13") (pintype "input"))
      (node (ref "RN5") (pin "6") (pinfunction "2_6") (pintype "passive"))
      (node (ref "RN6") (pin "6") (pinfunction "2_6") (pintype "passive"))
    )
    (net (code "84") (name "Net-(IC6B-I)") (class "Default")
      (node (ref "IC6") (pin "11") (pinfunction "I_11") (pintype "input"))
      (node (ref "RN5") (pin "5") (pinfunction "2_5") (pintype "passive"))
      (node (ref "RN6") (pin "5") (pinfunction "2_5") (pintype "passive"))
    )
    (net (code "85") (name "Net-(JP11-Pad3)") (class "Default")
      (node (ref "JP11") (pin "3") (pinfunction "3_3") (pintype "passive"))
      (node (ref "RN2") (pin "1") (pinfunction "1_1") (pintype "passive"))
    )
    (net (code "86") (name "Net-(JP13-Pad3)") (class "Default")
      (node (ref "JP13") (pin "3") (pinfunction "3_3") (pintype "passive"))
      (node (ref "RN1") (pin "1") (pinfunction "1_1") (pintype "passive"))
    )
    (net (code "87") (name "Net-(RN1B-1)") (class "Default")
      (node (ref "JP13") (pin "6") (pinfunction "6_6") (pintype "passive"))
      (node (ref "RN1") (pin "2") (pinfunction "1_2") (pintype "passive"))
    )
    (net (code "88") (name "Net-(RN1C-1)") (class "Default")
      (node (ref "JP14") (pin "3") (pinfunction "3_3") (pintype "passive"))
      (node (ref "RN1") (pin "3") (pinfunction "1_3") (pintype "passive"))
    )
    (net (code "89") (name "Net-(RN1D-1)") (class "Default")
      (node (ref "JP14") (pin "6") (pinfunction "6_6") (pintype "passive"))
      (node (ref "RN1") (pin "4") (pinfunction "1_4") (pintype "passive"))
    )
    (net (code "90") (name "Net-(RN2B-1)") (class "Default")
      (node (ref "JP11") (pin "6") (pinfunction "6_6") (pintype "passive"))
      (node (ref "RN2") (pin "2") (pinfunction "1_2") (pintype "passive"))
    )
    (net (code "91") (name "Net-(RN2C-1)") (class "Default")
      (node (ref "JP12") (pin "3") (pinfunction "3_3") (pintype "passive"))
      (node (ref "RN2") (pin "3") (pinfunction "1_3") (pintype "passive"))
    )
    (net (code "92") (name "Net-(RN2D-1)") (class "Default")
      (node (ref "JP12") (pin "6") (pinfunction "6_6") (pintype "passive"))
      (node (ref "RN2") (pin "4") (pinfunction "1_4") (pintype "passive"))
    )
    (net (code "93") (name "Net-(RN7A-2)") (class "Default")
      (node (ref "C3") (pin "2") (pinfunction "2_2") (pintype "passive"))
      (node (ref "RN7") (pin "8") (pinfunction "2_8") (pintype "passive"))
    )
    (net (code "94") (name "Net-(RN7B-1)") (class "Default")
      (node (ref "D5") (pin "C") (pinfunction "C_C") (pintype "passive"))
      (node (ref "D6") (pin "A") (pinfunction "A_A") (pintype "passive"))
      (node (ref "RN7") (pin "2") (pinfunction "1_2") (pintype "passive"))
    )
    (net (code "95") (name "Net-(RN7B-2)") (class "Default")
      (node (ref "C15") (pin "2") (pinfunction "2_2") (pintype "passive"))
      (node (ref "RN7") (pin "7") (pinfunction "2_7") (pintype "passive"))
    )
    (net (code "96") (name "Net-(RN7C-1)") (class "Default")
      (node (ref "D3") (pin "C") (pinfunction "C_C") (pintype "passive"))
      (node (ref "D4") (pin "A") (pinfunction "A_A") (pintype "passive"))
      (node (ref "RN7") (pin "3") (pinfunction "1_3") (pintype "passive"))
    )
    (net (code "97") (name "Net-(RN7C-2)") (class "Default")
      (node (ref "C9") (pin "2") (pinfunction "2_2") (pintype "passive"))
      (node (ref "RN7") (pin "6") (pinfunction "2_6") (pintype "passive"))
    )
    (net (code "98") (name "Net-(RN7D-1)") (class "Default")
      (node (ref "D7") (pin "C") (pinfunction "C_C") (pintype "passive"))
      (node (ref "D8") (pin "A") (pinfunction "A_A") (pintype "passive"))
      (node (ref "RN7") (pin "4") (pinfunction "1_4") (pintype "passive"))
    )
    (net (code "99") (name "Net-(RN7D-2)") (class "Default")
      (node (ref "C21") (pin "2") (pinfunction "2_2") (pintype "passive"))
      (node (ref "RN7") (pin "5") (pinfunction "2_5") (pintype "passive"))
    )
    (net (code "100") (name "Net-(RN9A-2)") (class "Default")
      (node (ref "JP15") (pin "5") (pinfunction "5_5") (pintype "passive"))
      (node (ref "RN9") (pin "8") (pinfunction "2_8") (pintype "passive"))
    )
    (net (code "101") (name "Net-(RN9B-2)") (class "Default")
      (node (ref "JP15") (pin "13") (pinfunction "13_13") (pintype "passive"))
      (node (ref "RN9") (pin "7") (pinfunction "2_7") (pintype "passive"))
    )
    (net (code "102") (name "Net-(RN9C-1)") (class "Default")
      (node (ref "JP15") (pin "6") (pinfunction "6_6") (pintype "passive"))
      (node (ref "RN9") (pin "3") (pinfunction "1_3") (pintype "passive"))
    )
    (net (code "103") (name "Net-(RN9D-1)") (class "Default")
      (node (ref "JP15") (pin "14") (pinfunction "14_14") (pintype "passive"))
      (node (ref "RN9") (pin "4") (pinfunction "1_4") (pintype "passive"))
    )
    (net (code "104") (name "VCC") (class "Default")
      (node (ref "C25") (pin "1") (pinfunction "1_1") (pintype "passive"))
      (node (ref "IC4") (pin "14") (pinfunction "VCC_14") (pintype "power_in"))
      (node (ref "RN10") (pin "1") (pinfunction "1_1") (pintype "passive"))
      (node (ref "RN10") (pin "2") (pinfunction "1_2") (pintype "passive"))
      (node (ref "RN10") (pin "5") (pinfunction "2_5") (pintype "passive"))
      (node (ref "RN10") (pin "6") (pinfunction "2_6") (pintype "passive"))
      (node (ref "RN9") (pin "1") (pinfunction "1_1") (pintype "passive"))
      (node (ref "RN9") (pin "2") (pinfunction "1_2") (pintype "passive"))
      (node (ref "RN9") (pin "5") (pinfunction "2_5") (pintype "passive"))
      (node (ref "RN9") (pin "6") (pinfunction "2_6") (pintype "passive"))
    )
    (net (code "105") (name "VDD") (class "Default")
      (node (ref "C10") (pin "1") (pinfunction "1_1") (pintype "passive"))
      (node (ref "C11") (pin "1") (pinfunction "1_1") (pintype "passive"))
      (node (ref "C12") (pin "+") (pinfunction "+_+") (pintype "passive"))
      (node (ref "C16") (pin "1") (pinfunction "1_1") (pintype "passive"))
      (node (ref "C17") (pin "1") (pinfunction "1_1") (pintype "passive"))
      (node (ref "C18") (pin "+") (pinfunction "+_+") (pintype "passive"))
      (node (ref "C22") (pin "1") (pinfunction "1_1") (pintype "passive"))
      (node (ref "C23") (pin "1") (pinfunction "1_1") (pintype "passive"))
      (node (ref "C24") (pin "+") (pinfunction "+_+") (pintype "passive"))
      (node (ref "C4") (pin "1") (pinfunction "1_1") (pintype "passive"))
      (node (ref "C5") (pin "1") (pinfunction "1_1") (pintype "passive"))
      (node (ref "C6") (pin "+") (pinfunction "+_+") (pintype "passive"))
      (node (ref "D1") (pin "A") (pinfunction "A_A") (pintype "passive"))
      (node (ref "D3") (pin "A") (pinfunction "A_A") (pintype "passive"))
      (node (ref "D5") (pin "A") (pinfunction "A_A") (pintype "passive"))
      (node (ref "D7") (pin "A") (pinfunction "A_A") (pintype "passive"))
      (node (ref "IC1") (pin "19") (pinfunction "VS_B_19") (pintype "power_in"))
      (node (ref "IC1") (pin "2") (pinfunction "VS_A_2") (pintype "power_in"))
      (node (ref "IC2") (pin "19") (pinfunction "VS_B_19") (pintype "power_in"))
      (node (ref "IC2") (pin "2") (pinfunction "VS_A_2") (pintype "power_in"))
      (node (ref "IC3") (pin "19") (pinfunction "VS_B_19") (pintype "power_in"))
      (node (ref "IC3") (pin "2") (pinfunction "VS_A_2") (pintype "power_in"))
      (node (ref "IC5") (pin "19") (pinfunction "VS_B_19") (pintype "power_in"))
      (node (ref "IC5") (pin "2") (pinfunction "VS_A_2") (pintype "power_in"))
      (node (ref "X2") (pin "1") (pinfunction "KL_1") (pintype "passive"))
    )
  )
)
